# taller_1.net
KiCad netlist of a schematic drawn in EAGLE
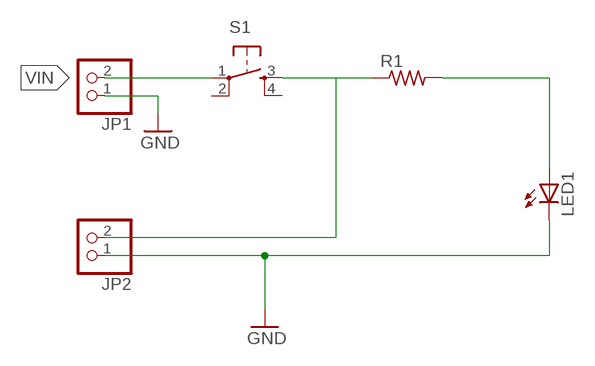
[diagram p0: schematic, sheet 1]

(export (version "E")
  (design (tool "Eeschema 10.0.6"))
  (components
    (comp (ref "JP1")
      (value "PINHD-1X2/90")
      (footprint "eagle-import:1X02_90")
      (libsource (lib "eagle-import") (part "PINHD-1X2/90"))
    )
    (comp (ref "JP2")
      (value "PINHD-1X2/90")
      (footprint "eagle-import:1X02_90")
      (libsource (lib "eagle-import") (part "PINHD-1X2/90"))
    )
    (comp (ref "LED1")
      (value "LED5MM")
      (footprint "eagle-import:LED5MM")
      (libsource (lib "eagle-import") (part "LED5MM"))
    )
    (comp (ref "R1")
      (value "R-US_0207/15")
      (footprint "eagle-import:0207_15")
      (libsource (lib "eagle-import") (part "R-US_0207/15"))
    )
    (comp (ref "S1")
      (value "TAC_SWITCHPTH")
      (footprint "eagle-import:TACTILE-PTH")
      (libsource (lib "eagle-import") (part "TAC_SWITCHPTH"))
    )
  )
  (nets
    (net (code "1") (name "GND") (class "Default")
      (node (ref "JP1") (pin "1") (pinfunction "1_1") (pintype "passive"))
      (node (ref "JP2") (pin "1") (pinfunction "1_1") (pintype "passive"))
      (node (ref "LED1") (pin "K") (pinfunction "C_K") (pintype "passive"))
    )
    (net (code "2") (name "Net-(JP2-Pad2)") (class "Default")
      (node (ref "JP2") (pin "2") (pinfunction "2_2") (pintype "passive"))
      (node (ref "R1") (pin "1") (pinfunction "1_1") (pintype "passive"))
      (node (ref "S1") (pin "3") (pinfunction "3_3") (pintype "passive"))
    )
    (net (code "3") (name "Net-(LED1-PadA)") (class "Default")
      (node (ref "LED1") (pin "A") (pinfunction "A_A") (pintype "passive"))
      (node (ref "R1") (pin "2") (pinfunction "2_2") (pintype "passive"))
    )
    (net (code "4") (name "VIN") (class "Default")
      (node (ref "JP1") (pin "2") (pinfunction "2_2") (pintype "passive"))
      (node (ref "S1") (pin "1") (pinfunction "1_1") (pintype "passive"))
    )
    (net (code "5") (name "unconnected-(S1-Pad2)") (class "Default")
      (node (ref "S1") (pin "2") (pinfunction "2_2") (pintype "passive"))
    )
    (net (code "6") (name "unconnected-(S1-Pad4)") (class "Default")
      (node (ref "S1") (pin "4") (pinfunction "4_4") (pintype "passive"))
    )
  )
)
